# Phase_3_1_Form_Factor_2.net
KiCad netlist of a schematic drawn in EAGLE
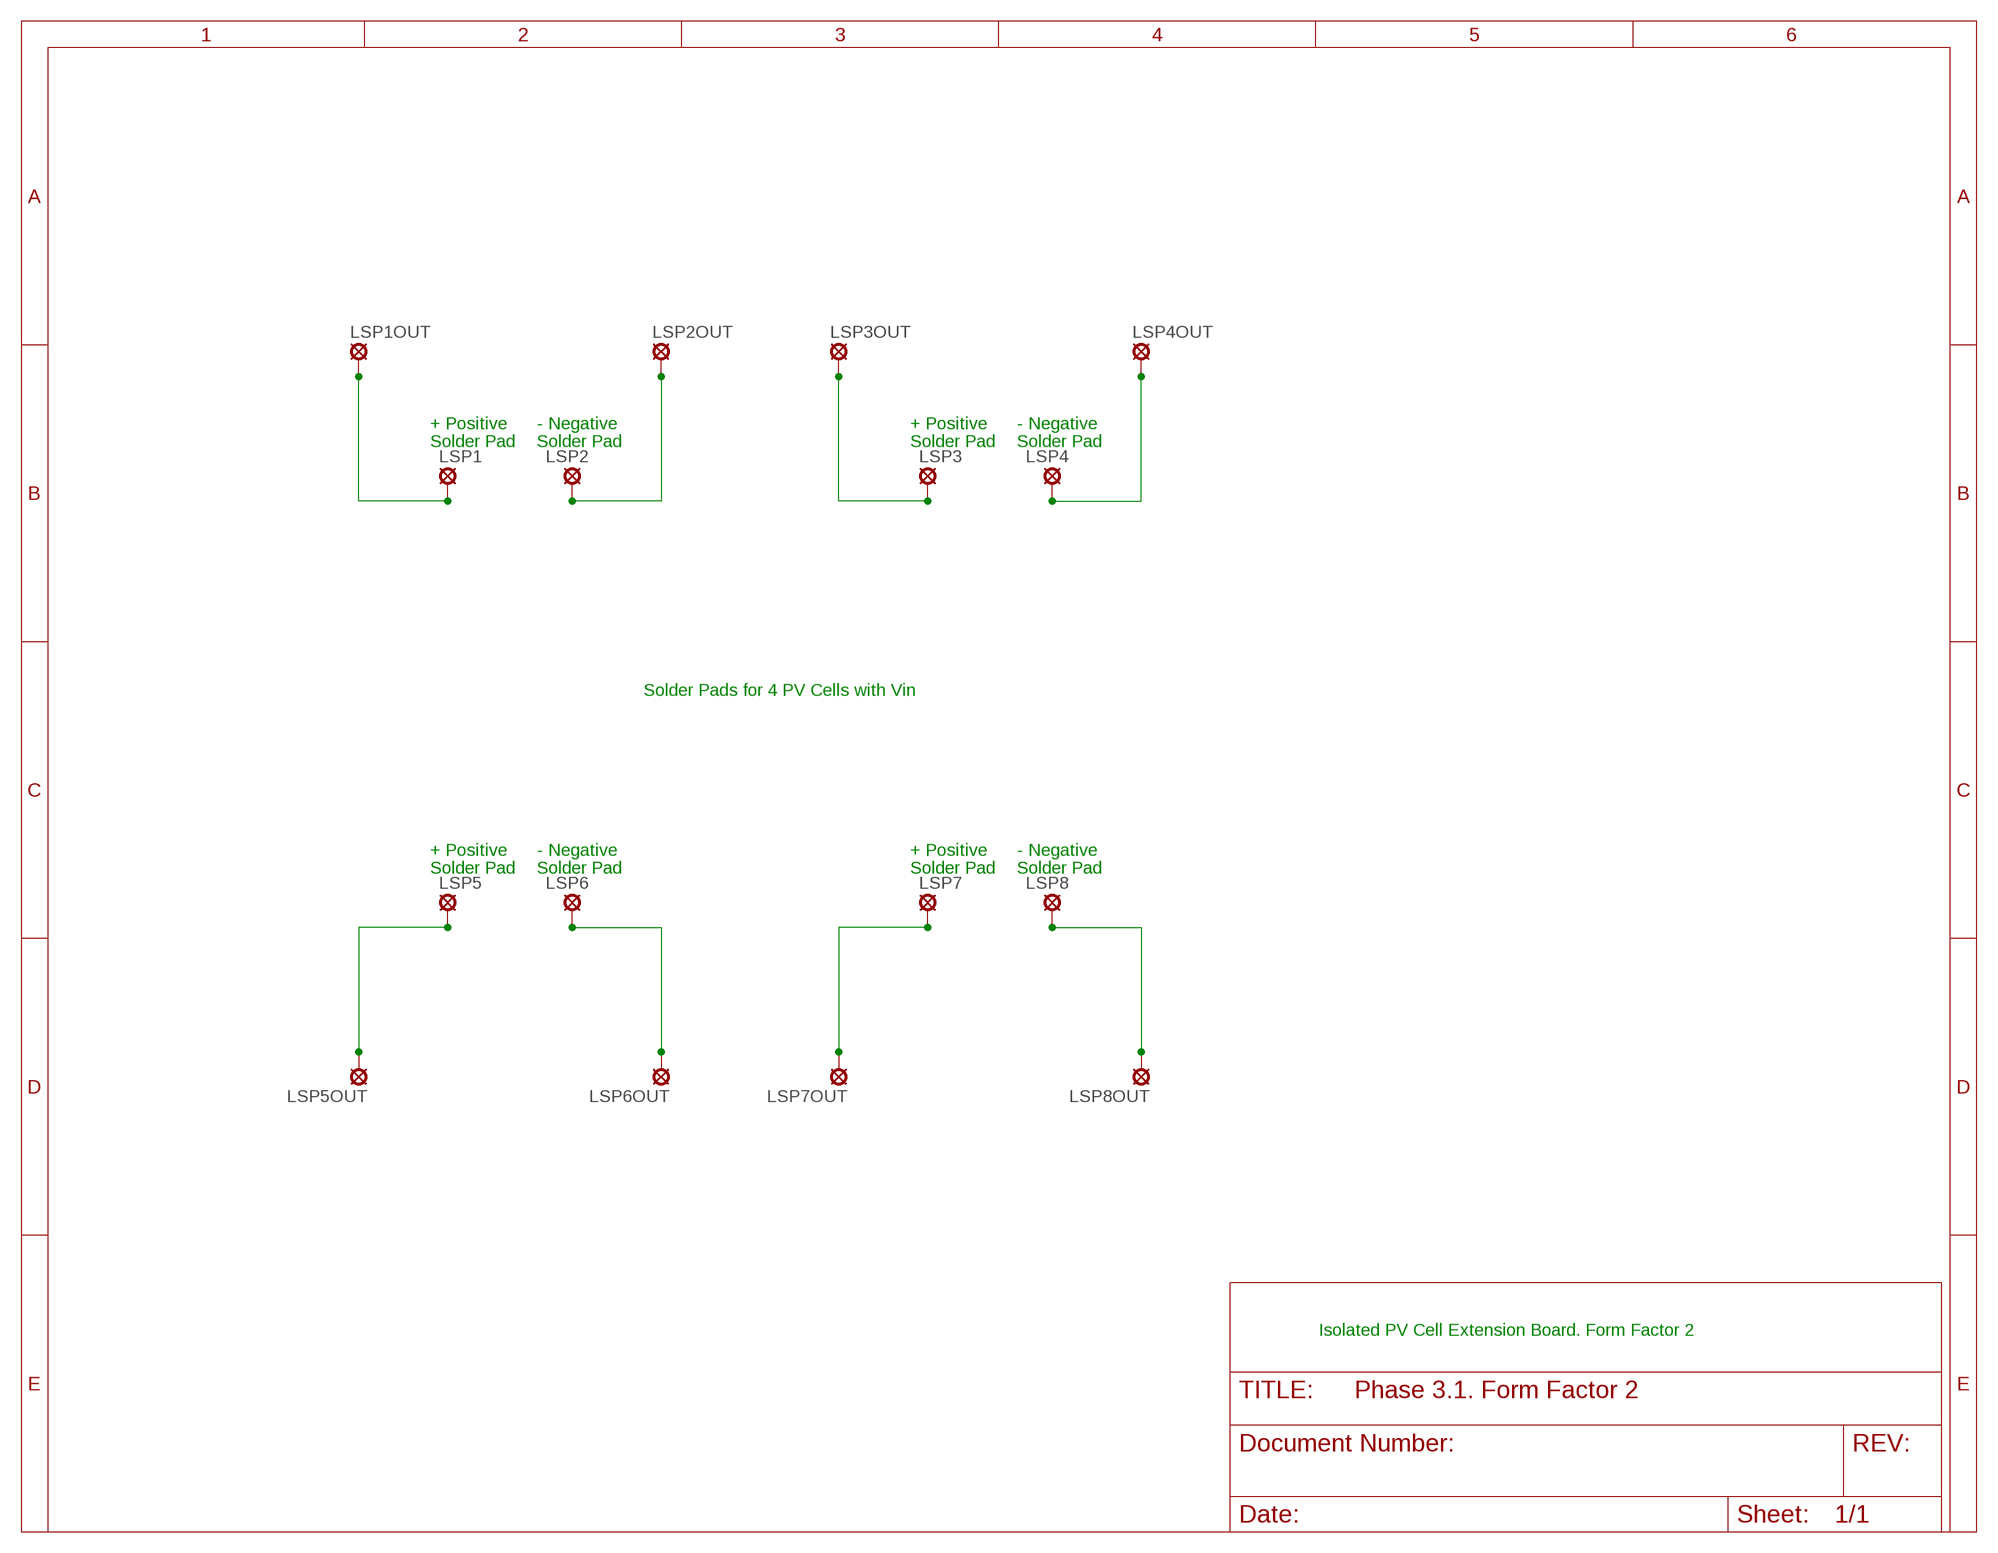
[diagram p0: schematic, sheet 1]

(export (version "E")
  (design (tool "Eeschema 10.0.6"))
  (components
    (comp (ref "LSP1")
      (value "LSP10")
      (footprint "eagle-import:LSP10")
      (libsource (lib "eagle-import") (part "LSP10"))
    )
    (comp (ref "LSP1OUT")
      (value "LSP10")
      (footprint "eagle-import:LSP10")
      (libsource (lib "eagle-import") (part "LSP10"))
    )
    (comp (ref "LSP2")
      (value "LSP10")
      (footprint "eagle-import:LSP10")
      (libsource (lib "eagle-import") (part "LSP10"))
    )
    (comp (ref "LSP2OUT")
      (value "LSP10")
      (footprint "eagle-import:LSP10")
      (libsource (lib "eagle-import") (part "LSP10"))
    )
    (comp (ref "LSP3")
      (value "LSP10")
      (footprint "eagle-import:LSP10")
      (libsource (lib "eagle-import") (part "LSP10"))
    )
    (comp (ref "LSP3OUT")
      (value "LSP10")
      (footprint "eagle-import:LSP10")
      (libsource (lib "eagle-import") (part "LSP10"))
    )
    (comp (ref "LSP4")
      (value "LSP10")
      (footprint "eagle-import:LSP10")
      (libsource (lib "eagle-import") (part "LSP10"))
    )
    (comp (ref "LSP4OUT")
      (value "LSP10")
      (footprint "eagle-import:LSP10")
      (libsource (lib "eagle-import") (part "LSP10"))
    )
    (comp (ref "LSP5")
      (value "LSP10")
      (footprint "eagle-import:LSP10")
      (libsource (lib "eagle-import") (part "LSP10"))
    )
    (comp (ref "LSP5OUT")
      (value "LSP10")
      (footprint "eagle-import:LSP10")
      (libsource (lib "eagle-import") (part "LSP10"))
    )
    (comp (ref "LSP6")
      (value "LSP10")
      (footprint "eagle-import:LSP10")
      (libsource (lib "eagle-import") (part "LSP10"))
    )
    (comp (ref "LSP6OUT")
      (value "LSP10")
      (footprint "eagle-import:LSP10")
      (libsource (lib "eagle-import") (part "LSP10"))
    )
    (comp (ref "LSP7")
      (value "LSP10")
      (footprint "eagle-import:LSP10")
      (libsource (lib "eagle-import") (part "LSP10"))
    )
    (comp (ref "LSP7OUT")
      (value "LSP10")
      (footprint "eagle-import:LSP10")
      (libsource (lib "eagle-import") (part "LSP10"))
    )
    (comp (ref "LSP8")
      (value "LSP10")
      (footprint "eagle-import:LSP10")
      (libsource (lib "eagle-import") (part "LSP10"))
    )
    (comp (ref "LSP8OUT")
      (value "LSP10")
      (footprint "eagle-import:LSP10")
      (libsource (lib "eagle-import") (part "LSP10"))
    )
  )
  (nets
    (net (code "1") (name "Net-(LSP1-PadMP)") (class "Default")
      (node (ref "LSP1") (pin "MP") (pinfunction "MP_MP") (pintype "passive"))
      (node (ref "LSP1OUT") (pin "MP") (pinfunction "MP_MP") (pintype "passive"))
    )
    (net (code "2") (name "Net-(LSP2-PadMP)") (class "Default")
      (node (ref "LSP2") (pin "MP") (pinfunction "MP_MP") (pintype "passive"))
      (node (ref "LSP2OUT") (pin "MP") (pinfunction "MP_MP") (pintype "passive"))
    )
    (net (code "3") (name "Net-(LSP3-PadMP)") (class "Default")
      (node (ref "LSP3") (pin "MP") (pinfunction "MP_MP") (pintype "passive"))
      (node (ref "LSP3OUT") (pin "MP") (pinfunction "MP_MP") (pintype "passive"))
    )
    (net (code "4") (name "Net-(LSP4-PadMP)") (class "Default")
      (node (ref "LSP4") (pin "MP") (pinfunction "MP_MP") (pintype "passive"))
      (node (ref "LSP4OUT") (pin "MP") (pinfunction "MP_MP") (pintype "passive"))
    )
    (net (code "5") (name "Net-(LSP5-PadMP)") (class "Default")
      (node (ref "LSP5") (pin "MP") (pinfunction "MP_MP") (pintype "passive"))
      (node (ref "LSP5OUT") (pin "MP") (pinfunction "MP_MP") (pintype "passive"))
    )
    (net (code "6") (name "Net-(LSP6-PadMP)") (class "Default")
      (node (ref "LSP6") (pin "MP") (pinfunction "MP_MP") (pintype "passive"))
      (node (ref "LSP6OUT") (pin "MP") (pinfunction "MP_MP") (pintype "passive"))
    )
    (net (code "7") (name "Net-(LSP7-PadMP)") (class "Default")
      (node (ref "LSP7") (pin "MP") (pinfunction "MP_MP") (pintype "passive"))
      (node (ref "LSP7OUT") (pin "MP") (pinfunction "MP_MP") (pintype "passive"))
    )
    (net (code "8") (name "Net-(LSP8-PadMP)") (class "Default")
      (node (ref "LSP8") (pin "MP") (pinfunction "MP_MP") (pintype "passive"))
      (node (ref "LSP8OUT") (pin "MP") (pinfunction "MP_MP") (pintype "passive"))
    )
  )
)
